# KNoT-Gateway_Mini_Starter_Board.net
KiCad netlist of a schematic drawn in Altium Designer
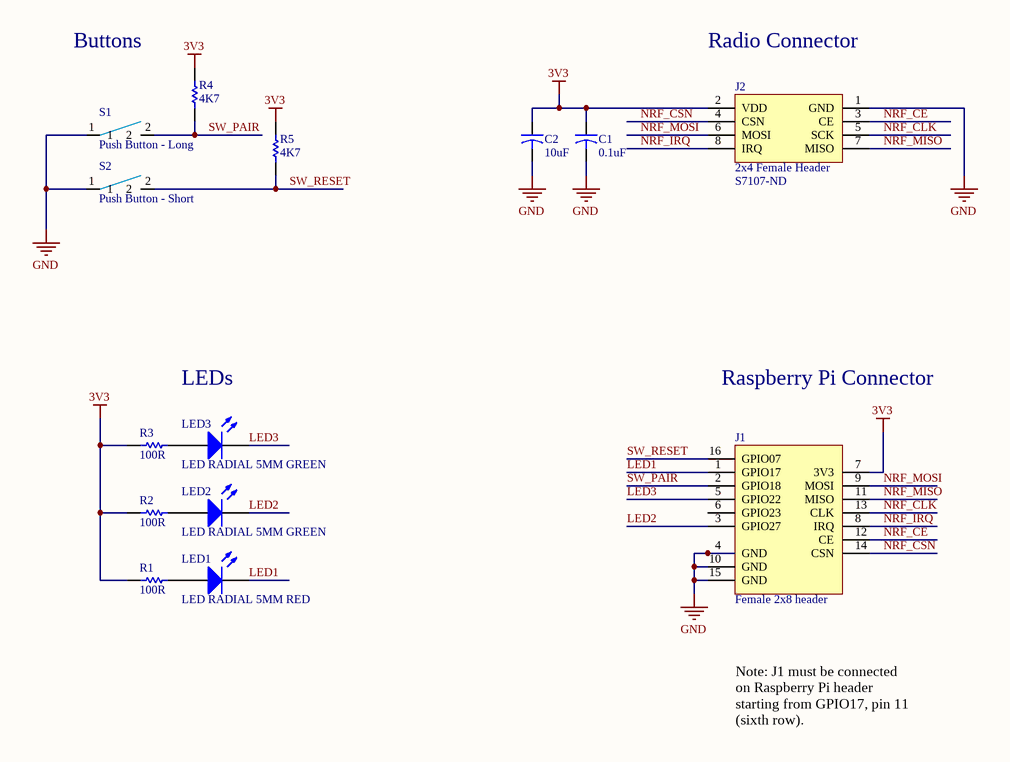
[diagram p0: KNoT-Gateway Mini Starter Board.SchDoc]

(export (version "E")
  (design (tool "Eeschema 10.0.6"))
  (components
    (comp (ref "C1")
      (value "0.1uF")
      (footprint "0805_CAPS")
      (description "0.1µF  Ceramic Capacitor 0805")
      (fields (field (name "Comment") "Cap 0805 0.1uF"))
      (libsource (lib "KNoT-Gateway Library") (part "Cap_0805_0.1uF"))
    )
    (comp (ref "C2")
      (value "10uF")
      (footprint "0805_CAPS")
      (description "10uF Ceramic Capacitor 0805")
      (fields (field (name "Comment") "Cap 0805 10uF"))
      (libsource (lib "KNoT-Gateway Library") (part "Cap_0805_10uF"))
    )
    (comp (ref "J1")
      (value "Female 2x8 header")
      (footprint "FEMALE HEADER 2X8")
      (description "Female Bottom 2x4 Header")
      (libsource (lib "KNoT-Gateway Library") (part "2x8 RPi Header"))
    )
    (comp (ref "J2")
      (value "2x4 Female Header")
      (footprint "nRF24L01+PA+LNA")
      (description "nRF24L01 2x4 HEADER")
      (fields (field (name "SUPPLIER PART NUMBER 1") "S7107-ND"))
      (libsource (lib "KNoT-Gateway Library") (part "nRF24L01+"))
    )
    (comp (ref "LED1")
      (value "LED RADIAL 5MM RED")
      (footprint "LED RADIAL 5MM RED")
      (description "LED RADIAL")
      (libsource (lib "KNoT-Gateway Library") (part "LED RADIAL 5MM RED"))
    )
    (comp (ref "LED2")
      (value "LED RADIAL 5MM GREEN")
      (footprint "LED RADIAL 5MM GREEN")
      (description "LED RADIAL")
      (libsource (lib "KNoT-Gateway Library") (part "LED RADIAL 5MM GREEN"))
    )
    (comp (ref "LED3")
      (value "LED RADIAL 5MM GREEN")
      (footprint "LED RADIAL 5MM GREEN")
      (description "LED RADIAL")
      (libsource (lib "KNoT-Gateway Library") (part "LED RADIAL 5MM GREEN"))
    )
    (comp (ref "R1")
      (value "100R")
      (footprint "0805_RES")
      (fields (field (name "Comment") "RES_0805"))
      (libsource (lib "KNoT-Gateway Library") (part "RES_0805"))
    )
    (comp (ref "R2")
      (value "100R")
      (footprint "0805_RES")
      (fields (field (name "Comment") "RES_0805"))
      (libsource (lib "KNoT-Gateway Library") (part "RES_0805"))
    )
    (comp (ref "R3")
      (value "100R")
      (footprint "0805_RES")
      (fields (field (name "Comment") "RES_0805"))
      (libsource (lib "KNoT-Gateway Library") (part "RES_0805"))
    )
    (comp (ref "R4")
      (value "4K7")
      (footprint "0805_RES")
      (fields (field (name "Comment") "RES_0805"))
      (libsource (lib "KNoT-Gateway Library") (part "RES_0805"))
    )
    (comp (ref "R5")
      (value "4K7")
      (footprint "0805_RES")
      (fields (field (name "Comment") "RES_0805"))
      (libsource (lib "KNoT-Gateway Library") (part "RES_0805"))
    )
    (comp (ref "S1")
      (value "Push Button - Long")
      (footprint "Tac Push Button L")
      (description "Tactile Push Button Right Angle")
      (libsource (lib "KNoT-Gateway Library") (part "Push Button L"))
    )
    (comp (ref "S2")
      (value "Push Button - Short")
      (footprint "Tac Push Button S")
      (description "Tactile Push Button Right Angle")
      (libsource (lib "KNoT-Gateway Library") (part "Push Button S"))
    )
  )
  (nets
    (net (code "1") (name "/LED1") (class "Default")
      (node (ref "J1") (pin "1") (pinfunction "GPIO17_1") (pintype "passive"))
      (node (ref "LED1") (pin "2") (pinfunction "K_2") (pintype "passive"))
    )
    (net (code "2") (name "/LED2") (class "Default")
      (node (ref "J1") (pin "3") (pinfunction "GPIO27_3") (pintype "passive"))
      (node (ref "LED2") (pin "2") (pinfunction "K_2") (pintype "passive"))
    )
    (net (code "3") (name "/LED3") (class "Default")
      (node (ref "J1") (pin "5") (pinfunction "GPIO22_5") (pintype "passive"))
      (node (ref "LED3") (pin "2") (pinfunction "K_2") (pintype "passive"))
    )
    (net (code "4") (name "/NRF_CE") (class "Default")
      (node (ref "J1") (pin "12") (pinfunction "CE_12") (pintype "passive"))
      (node (ref "J2") (pin "3") (pinfunction "CE_3") (pintype "passive"))
    )
    (net (code "5") (name "/NRF_CLK") (class "Default")
      (node (ref "J1") (pin "13") (pinfunction "CLK_13") (pintype "passive"))
      (node (ref "J2") (pin "5") (pinfunction "SCK_5") (pintype "passive"))
    )
    (net (code "6") (name "/NRF_CSN") (class "Default")
      (node (ref "J1") (pin "14") (pinfunction "CSN_14") (pintype "passive"))
      (node (ref "J2") (pin "4") (pinfunction "CSN_4") (pintype "passive"))
    )
    (net (code "7") (name "/NRF_IRQ") (class "Default")
      (node (ref "J1") (pin "8") (pinfunction "IRQ_8") (pintype "passive"))
      (node (ref "J2") (pin "8") (pinfunction "IRQ_8") (pintype "passive"))
    )
    (net (code "8") (name "/NRF_MISO") (class "Default")
      (node (ref "J1") (pin "11") (pinfunction "MISO_11") (pintype "passive"))
      (node (ref "J2") (pin "7") (pinfunction "MISO_7") (pintype "passive"))
    )
    (net (code "9") (name "/NRF_MOSI") (class "Default")
      (node (ref "J1") (pin "9") (pinfunction "MOSI_9") (pintype "passive"))
      (node (ref "J2") (pin "6") (pinfunction "MOSI_6") (pintype "passive"))
    )
    (net (code "10") (name "/SW_PAIR") (class "Default")
      (node (ref "J1") (pin "2") (pinfunction "GPIO18_2") (pintype "passive"))
      (node (ref "R4") (pin "1") (pinfunction "1_1") (pintype "passive"))
      (node (ref "S1") (pin "2") (pinfunction "2_2") (pintype "passive"))
    )
    (net (code "11") (name "/SW_RESET") (class "Default")
      (node (ref "J1") (pin "16") (pinfunction "GPIO07_16") (pintype "passive"))
      (node (ref "R5") (pin "1") (pinfunction "1_1") (pintype "passive"))
      (node (ref "S2") (pin "2") (pinfunction "2_2") (pintype "passive"))
    )
    (net (code "12") (name "3V3") (class "Default")
      (node (ref "C1") (pin "1") (pinfunction "1_1") (pintype "passive"))
      (node (ref "C2") (pin "1") (pinfunction "1_1") (pintype "passive"))
      (node (ref "J1") (pin "7") (pinfunction "3V3_7") (pintype "passive"))
      (node (ref "J2") (pin "2") (pinfunction "VDD_2") (pintype "passive"))
      (node (ref "R1") (pin "2") (pinfunction "2_2") (pintype "passive"))
      (node (ref "R2") (pin "2") (pinfunction "2_2") (pintype "passive"))
      (node (ref "R3") (pin "2") (pinfunction "2_2") (pintype "passive"))
      (node (ref "R4") (pin "2") (pinfunction "2_2") (pintype "passive"))
      (node (ref "R5") (pin "2") (pinfunction "2_2") (pintype "passive"))
    )
    (net (code "13") (name "GND") (class "Default")
      (node (ref "C1") (pin "2") (pinfunction "2_2") (pintype "passive"))
      (node (ref "C2") (pin "2") (pinfunction "2_2") (pintype "passive"))
      (node (ref "J1") (pin "10") (pinfunction "GND_10") (pintype "passive"))
      (node (ref "J1") (pin "15") (pinfunction "GND_15") (pintype "passive"))
      (node (ref "J1") (pin "4") (pinfunction "GND_4") (pintype "passive"))
      (node (ref "J2") (pin "1") (pinfunction "GND_1") (pintype "passive"))
      (node (ref "S1") (pin "1") (pinfunction "1_1") (pintype "passive"))
      (node (ref "S2") (pin "1") (pinfunction "1_1") (pintype "passive"))
    )
    (net (code "14") (name "Net-(LED1-A)") (class "Default")
      (node (ref "LED1") (pin "1") (pinfunction "A_1") (pintype "passive"))
      (node (ref "R1") (pin "1") (pinfunction "1_1") (pintype "passive"))
    )
    (net (code "15") (name "Net-(LED2-A)") (class "Default")
      (node (ref "LED2") (pin "1") (pinfunction "A_1") (pintype "passive"))
      (node (ref "R2") (pin "1") (pinfunction "1_1") (pintype "passive"))
    )
    (net (code "16") (name "Net-(LED3-A)") (class "Default")
      (node (ref "LED3") (pin "1") (pinfunction "A_1") (pintype "passive"))
      (node (ref "R3") (pin "1") (pinfunction "1_1") (pintype "passive"))
    )
    (net (code "17") (name "unconnected-(J1-GPIO23-Pad6)") (class "Default")
      (node (ref "J1") (pin "6") (pinfunction "GPIO23_6") (pintype "passive"))
    )
  )
)
